# LM2621.net
KiCad netlist of a schematic drawn in EAGLE
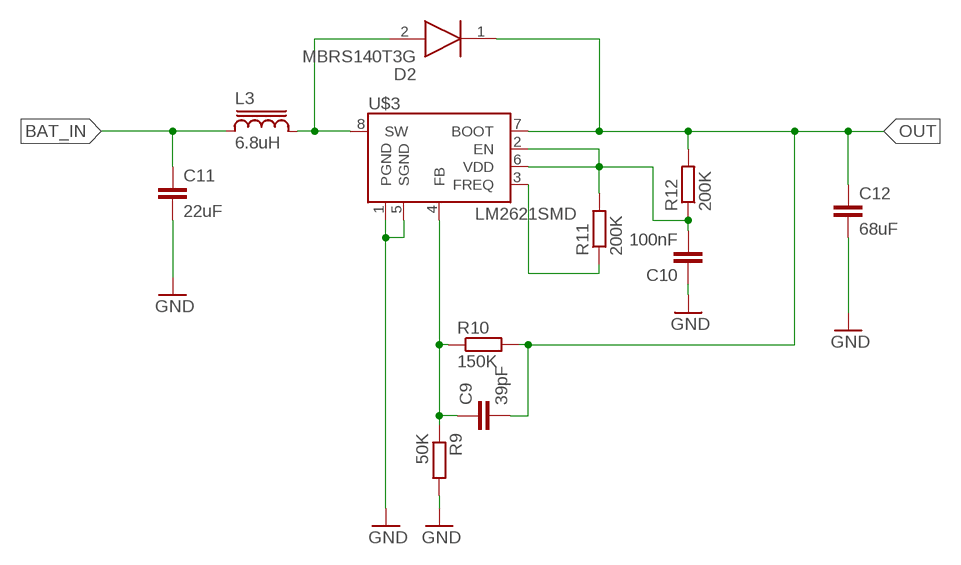
[diagram p0: schematic, sheet 1]

(export (version "E")
  (design (tool "Eeschema 10.0.6"))
  (components
    (comp (ref "C9")
      (value "39pF")
      (footprint "eagle-import:C0805")
      (libsource (lib "eagle-import") (part "C-EUC0805"))
    )
    (comp (ref "C10")
      (value "100nF")
      (footprint "eagle-import:C0805")
      (libsource (lib "eagle-import") (part "C-EUC0805"))
    )
    (comp (ref "C11")
      (value "22uF")
      (footprint "eagle-import:C1210")
      (libsource (lib "eagle-import") (part "C-EUC1210"))
    )
    (comp (ref "C12")
      (value "68uF")
      (footprint "eagle-import:C1210")
      (libsource (lib "eagle-import") (part "C-EUC1210"))
    )
    (comp (ref "D2")
      (value "MBRS140T3G")
      (footprint "eagle-import:DIOM5436X247N")
      (fields (field (name "RS_PART_NUMBER") "5452074P"))
      (libsource (lib "eagle-import") (part "MBRS140T3G"))
    )
    (comp (ref "L3")
      (value "6.8uH")
      (footprint "eagle-import:SRR1280")
      (libsource (lib "eagle-import") (part "SRR1280"))
    )
    (comp (ref "R9")
      (value "50K")
      (footprint "eagle-import:R0805")
      (libsource (lib "eagle-import") (part "R-EU_R0805"))
    )
    (comp (ref "R10")
      (value "150K")
      (footprint "eagle-import:R0805")
      (libsource (lib "eagle-import") (part "R-EU_R0805"))
    )
    (comp (ref "R11")
      (value "200K")
      (footprint "eagle-import:R0805")
      (libsource (lib "eagle-import") (part "R-EU_R0805"))
    )
    (comp (ref "R12")
      (value "200K")
      (footprint "eagle-import:R0805")
      (libsource (lib "eagle-import") (part "R-EU_R0805"))
    )
    (comp (ref "U$3")
      (value "LM2621SMD")
      (footprint "eagle-import:MSOP-8")
      (libsource (lib "eagle-import") (part "LM2621SMD"))
    )
  )
  (nets
    (net (code "1") (name "BAT_IN") (class "Default")
      (node (ref "C11") (pin "1") (pinfunction "1_1") (pintype "passive"))
      (node (ref "L3") (pin "1") (pinfunction "1_1") (pintype "passive"))
    )
    (net (code "2") (name "GND") (class "Default")
      (node (ref "C10") (pin "1") (pinfunction "1_1") (pintype "passive"))
      (node (ref "C11") (pin "2") (pinfunction "2_2") (pintype "passive"))
      (node (ref "C12") (pin "2") (pinfunction "2_2") (pintype "passive"))
      (node (ref "R9") (pin "2") (pinfunction "2_2") (pintype "passive"))
      (node (ref "U$3") (pin "1") (pinfunction "PGND_1") (pintype "bidirectional"))
      (node (ref "U$3") (pin "5") (pinfunction "SGND_5") (pintype "bidirectional"))
    )
    (net (code "3") (name "Net-(D2-A)") (class "Default")
      (node (ref "D2") (pin "2") (pinfunction "A_2") (pintype "bidirectional"))
      (node (ref "L3") (pin "2") (pinfunction "2_2") (pintype "passive"))
      (node (ref "U$3") (pin "8") (pinfunction "SW_8") (pintype "bidirectional"))
    )
    (net (code "4") (name "Net-(U$3-EN)") (class "Default")
      (node (ref "C10") (pin "2") (pinfunction "2_2") (pintype "passive"))
      (node (ref "R11") (pin "2") (pinfunction "2_2") (pintype "passive"))
      (node (ref "R12") (pin "1") (pinfunction "1_1") (pintype "passive"))
      (node (ref "U$3") (pin "2") (pinfunction "EN_2") (pintype "bidirectional"))
      (node (ref "U$3") (pin "6") (pinfunction "VDD_6") (pintype "bidirectional"))
    )
    (net (code "5") (name "Net-(U$3-FB)") (class "Default")
      (node (ref "C9") (pin "1") (pinfunction "1_1") (pintype "passive"))
      (node (ref "R10") (pin "1") (pinfunction "1_1") (pintype "passive"))
      (node (ref "R9") (pin "1") (pinfunction "1_1") (pintype "passive"))
      (node (ref "U$3") (pin "4") (pinfunction "FB_4") (pintype "bidirectional"))
    )
    (net (code "6") (name "Net-(U$3-FREQ)") (class "Default")
      (node (ref "R11") (pin "1") (pinfunction "1_1") (pintype "passive"))
      (node (ref "U$3") (pin "3") (pinfunction "FREQ_3") (pintype "bidirectional"))
    )
    (net (code "7") (name "OUT") (class "Default")
      (node (ref "C12") (pin "1") (pinfunction "1_1") (pintype "passive"))
      (node (ref "C9") (pin "2") (pinfunction "2_2") (pintype "passive"))
      (node (ref "D2") (pin "1") (pinfunction "K_1") (pintype "bidirectional"))
      (node (ref "R10") (pin "2") (pinfunction "2_2") (pintype "passive"))
      (node (ref "R12") (pin "2") (pinfunction "2_2") (pintype "passive"))
      (node (ref "U$3") (pin "7") (pinfunction "BOOT_7") (pintype "bidirectional"))
    )
  )
)
